# Sheet2.net
KiCad netlist of a schematic drawn in Altium Designer
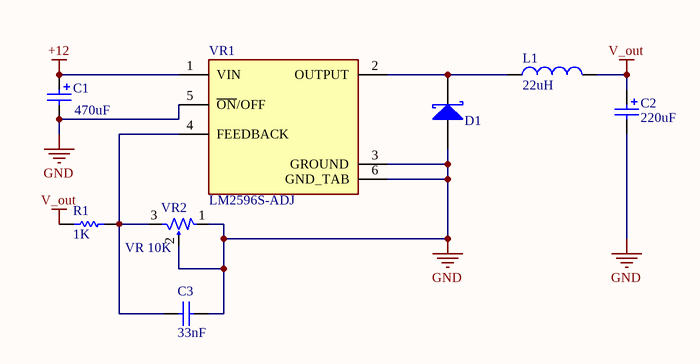
[diagram p0: Sheet2.SchDoc]

(export (version "E")
  (design (tool "Eeschema 10.0.6"))
  (components
    (comp (ref "C1")
      (value "470uF")
      (footprint "CAP ALU SIZE B")
      (description "Polarized Capacitor (Radial)")
      (fields (field (name "Comment") "Cap Pol SMD"))
      (libsource (lib "PIF_Library") (part "Cap Pol SMD"))
    )
    (comp (ref "C2")
      (value "220uF")
      (footprint "CAP ALU SIZE B")
      (description "Polarized Capacitor (Radial)")
      (fields (field (name "Comment") "Cap Pol SMD"))
      (libsource (lib "PIF_Library") (part "Cap Pol SMD"))
    )
    (comp (ref "C3")
      (value "33nF")
      (footprint "CAP-SM-0805")
      (description "Capacitor")
      (fields (field (name "Comment") "Cap Non-Pol SMD"))
      (libsource (lib "PIF_Library") (part "Cap Non-Pol SMD"))
    )
    (comp (ref "D1")
      (value "D Schottky")
      (footprint "SS34")
      (description "SS54-SMB")
      (fields (field (name "PUBLISHER") "Altium Limited"))
      (libsource (lib "PIF_Library") (part "D Schottky"))
    )
    (comp (ref "L1")
      (value "22uH")
      (footprint "INDUCTOR 12.5x12.5")
      (description "Inductor")
      (libsource (lib "PIF_Library") (part "Inductor"))
    )
    (comp (ref "R1")
      (value "1K")
      (footprint "RES-SM-0603")
      (description "Resistor")
      (fields (field (name "Comment") "RESISTOR SMD"))
      (libsource (lib "PIF_Library") (part "RESISTOR SMD"))
    )
    (comp (ref "VR1")
      (value "LM2596S-ADJ")
      (footprint "TO170P1524X483-6N")
      (description "SIMPLE SWITCHER&reg; 4.5V to 40V, 3A Low Component Count Step-Down Regulator")
      (fields (field (name "MP") "LM2596S-5.0/NOPB") (field (name "MF") "Texas Instruments"))
      (libsource (lib "LM2596S-5.0") (part "LM2596S-5.0"))
    )
    (comp (ref "VR2")
      (value "VR 10K")
      (footprint "Varistor 1")
      (description "Var Resistor")
      (fields (field (name "Comment") "10K"))
      (libsource (lib "PIF_Library") (part "Var Resistor"))
    )
  )
  (nets
    (net (code "1") (name "+12") (class "Default")
      (node (ref "C1") (pin "1") (pinfunction "1_1") (pintype "passive"))
      (node (ref "VR1") (pin "1") (pinfunction "VIN_1") (pintype "power_in"))
    )
    (net (code "2") (name "GND") (class "Default")
      (node (ref "C1") (pin "2") (pinfunction "2_2") (pintype "passive"))
      (node (ref "C2") (pin "2") (pinfunction "2_2") (pintype "passive"))
      (node (ref "C3") (pin "1") (pinfunction "1_1") (pintype "passive"))
      (node (ref "D1") (pin "1") (pinfunction "A_1") (pintype "passive"))
      (node (ref "VR1") (pin "3") (pinfunction "GROUND_3") (pintype "power_in"))
      (node (ref "VR1") (pin "5") (pinfunction "~{ON}/OFF_5") (pintype "power_in"))
      (node (ref "VR1") (pin "6") (pinfunction "GND_TAB_6") (pintype "power_in"))
      (node (ref "VR2") (pin "1") (pinfunction "1_1") (pintype "passive"))
      (node (ref "VR2") (pin "2") (pinfunction "2_2") (pintype "passive"))
    )
    (net (code "3") (name "Net-(D1-K)") (class "Default")
      (node (ref "D1") (pin "2") (pinfunction "K_2") (pintype "passive"))
      (node (ref "L1") (pin "1") (pinfunction "1_1") (pintype "passive"))
      (node (ref "VR1") (pin "2") (pinfunction "OUTPUT_2") (pintype "power_in"))
    )
    (net (code "4") (name "Net-(VR1-FEEDBACK)") (class "Default")
      (node (ref "C3") (pin "2") (pinfunction "2_2") (pintype "passive"))
      (node (ref "R1") (pin "2") (pinfunction "2_2") (pintype "passive"))
      (node (ref "VR1") (pin "4") (pinfunction "FEEDBACK_4") (pintype "power_in"))
      (node (ref "VR2") (pin "3") (pinfunction "3_3") (pintype "passive"))
    )
    (net (code "5") (name "V_out") (class "Default")
      (node (ref "C2") (pin "1") (pinfunction "1_1") (pintype "passive"))
      (node (ref "L1") (pin "2") (pinfunction "2_2") (pintype "passive"))
      (node (ref "R1") (pin "1") (pinfunction "1_1") (pintype "passive"))
    )
  )
)
